# design.net
KiCad netlist of a schematic drawn in Altium Designer
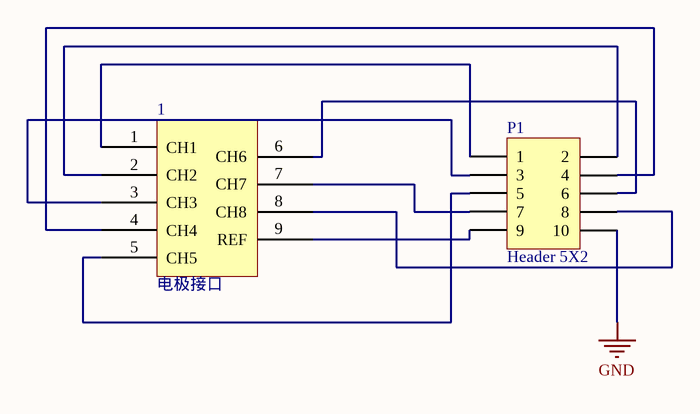
[diagram p0: 电极转接板.SchDoc]

(export (version "E")
  (design (tool "Eeschema 10.0.6"))
  (components
    (comp (ref "1") (value "电极接口") (footprint "电极接口") (libsource (lib "EEG") (part "电极接口")))
    (comp (ref "P1")
      (value "Header 5X2")
      (footprint "牛角直插10P")
      (description "Header, 5-Pin, Dual row")
      (fields (field (name "PUBLISHER") "Altium Limited"))
      (libsource (lib "Miscellaneous Connectors") (part "Header 5X2"))
    )
  )
  (nets
    (net (code "1") (name "GND") (class "Default")
      (node (ref "P1") (pin "10") (pinfunction "10_10") (pintype "passive"))
    )
    (net (code "2") (name "Net-(1-CH1)") (class "Default")
      (node (ref "1") (pin "1") (pinfunction "CH1_1") (pintype "passive"))
      (node (ref "P1") (pin "1") (pinfunction "1_1") (pintype "passive"))
    )
    (net (code "3") (name "Net-(1-CH2)") (class "Default")
      (node (ref "1") (pin "2") (pinfunction "CH2_2") (pintype "passive"))
      (node (ref "P1") (pin "2") (pinfunction "2_2") (pintype "passive"))
    )
    (net (code "4") (name "Net-(1-CH3)") (class "Default")
      (node (ref "1") (pin "3") (pinfunction "CH3_3") (pintype "passive"))
      (node (ref "P1") (pin "3") (pinfunction "3_3") (pintype "passive"))
    )
    (net (code "5") (name "Net-(1-CH4)") (class "Default")
      (node (ref "1") (pin "4") (pinfunction "CH4_4") (pintype "passive"))
      (node (ref "P1") (pin "4") (pinfunction "4_4") (pintype "passive"))
    )
    (net (code "6") (name "Net-(1-CH5)") (class "Default")
      (node (ref "1") (pin "5") (pinfunction "CH5_5") (pintype "passive"))
      (node (ref "P1") (pin "5") (pinfunction "5_5") (pintype "passive"))
    )
    (net (code "7") (name "Net-(1-CH6)") (class "Default")
      (node (ref "1") (pin "6") (pinfunction "CH6_6") (pintype "passive"))
      (node (ref "P1") (pin "6") (pinfunction "6_6") (pintype "passive"))
    )
    (net (code "8") (name "Net-(1-CH7)") (class "Default")
      (node (ref "1") (pin "7") (pinfunction "CH7_7") (pintype "passive"))
      (node (ref "P1") (pin "7") (pinfunction "7_7") (pintype "passive"))
    )
    (net (code "9") (name "Net-(1-CH8)") (class "Default")
      (node (ref "1") (pin "8") (pinfunction "CH8_8") (pintype "passive"))
      (node (ref "P1") (pin "8") (pinfunction "8_8") (pintype "passive"))
    )
    (net (code "10") (name "Net-(1-REF)") (class "Default")
      (node (ref "1") (pin "9") (pinfunction "REF_9") (pintype "passive"))
      (node (ref "P1") (pin "9") (pinfunction "9_9") (pintype "passive"))
    )
  )
)
